# rgb_led_watch.net
KiCad netlist of a schematic drawn in EAGLE
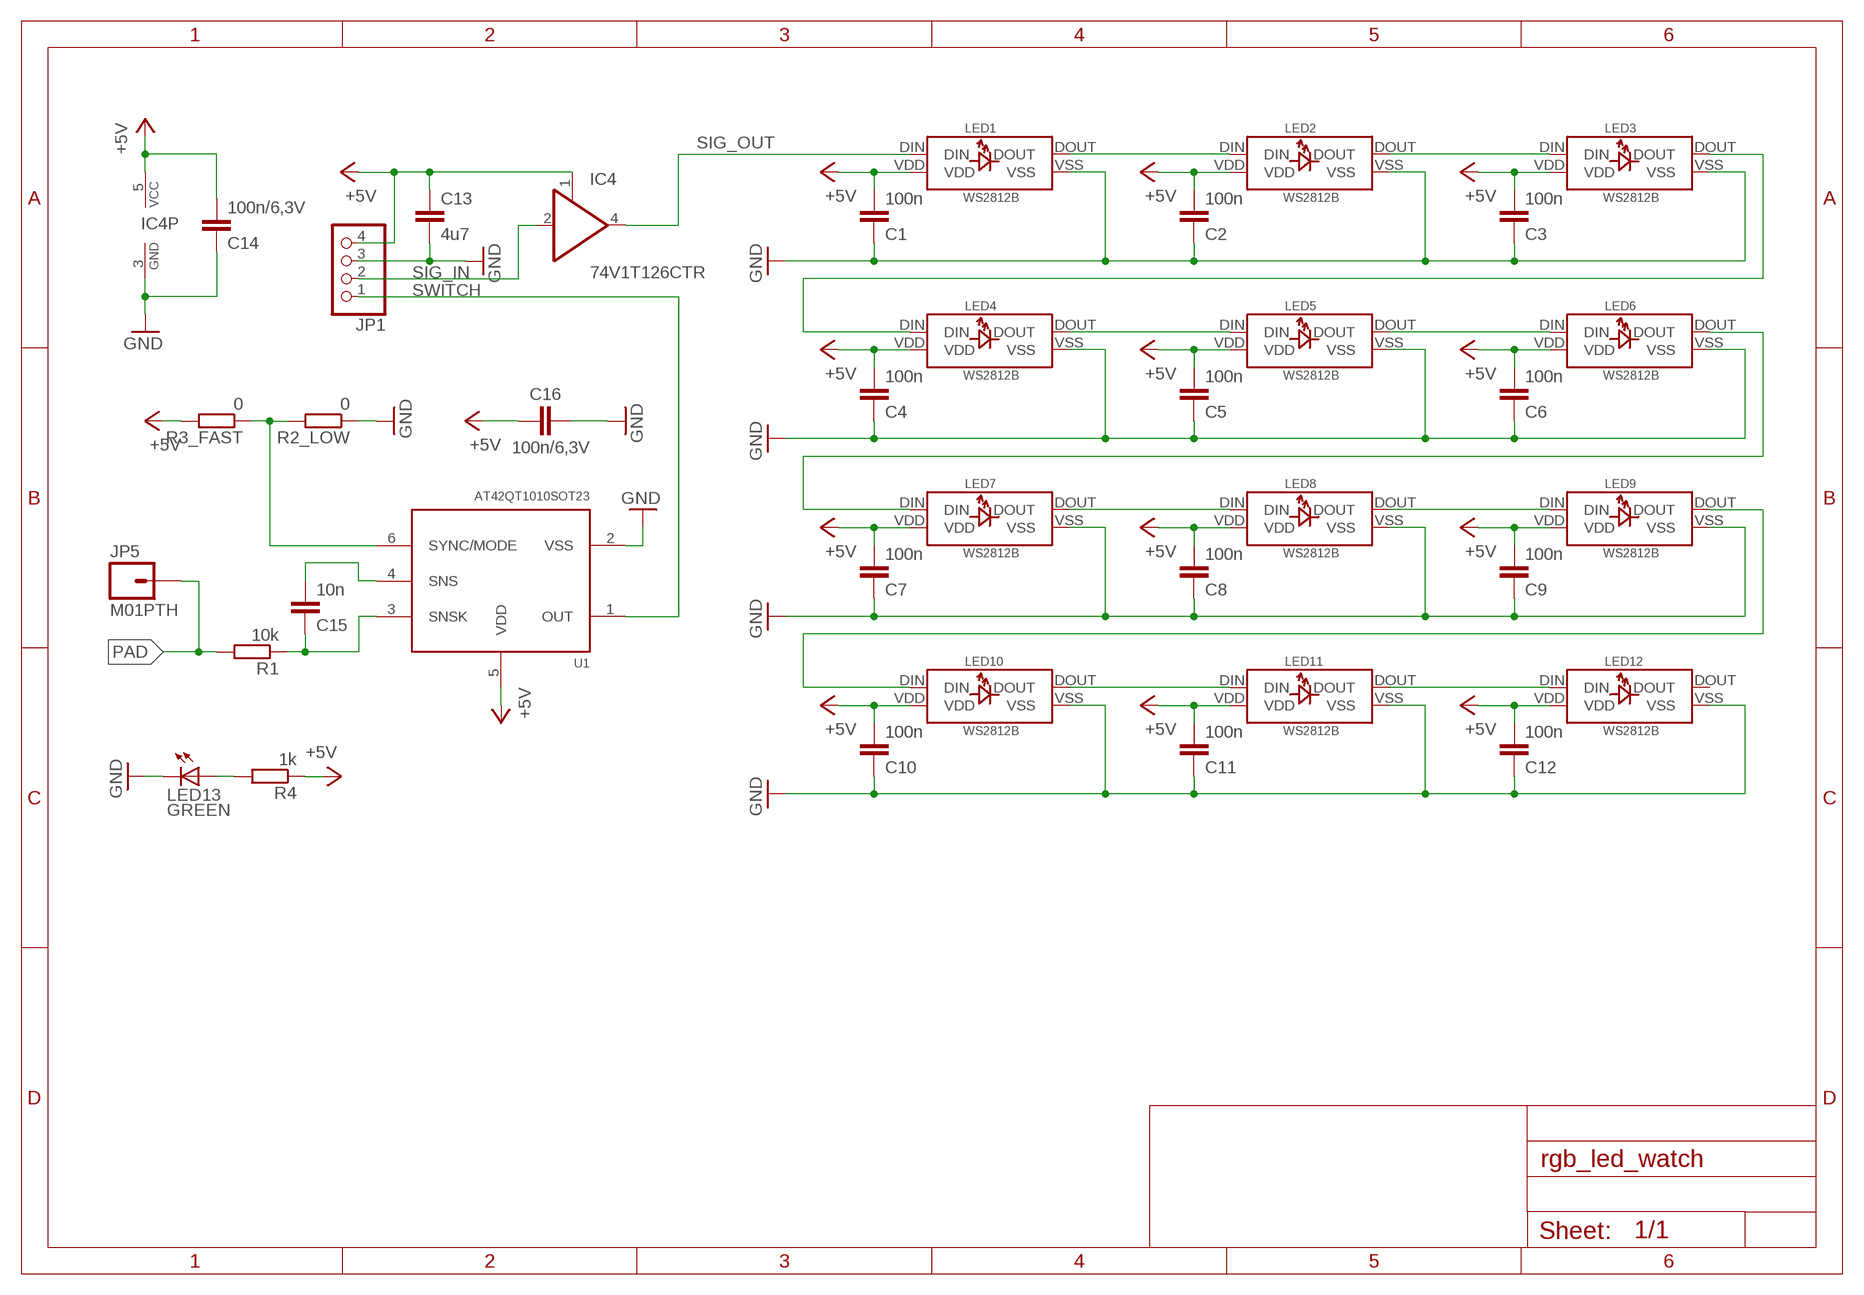
[diagram p0: schematic, sheet 1]

(export (version "E")
  (design (tool "Eeschema 10.0.6"))
  (components
    (comp (ref "C1")
      (value "100n")
      (footprint "eagle-import:C0603")
      (libsource (lib "eagle-import") (part "resistor_C-EUC0603"))
    )
    (comp (ref "C2")
      (value "100n")
      (footprint "eagle-import:C0603")
      (libsource (lib "eagle-import") (part "resistor_C-EUC0603"))
    )
    (comp (ref "C3")
      (value "100n")
      (footprint "eagle-import:C0603")
      (libsource (lib "eagle-import") (part "resistor_C-EUC0603"))
    )
    (comp (ref "C4")
      (value "100n")
      (footprint "eagle-import:C0603")
      (libsource (lib "eagle-import") (part "resistor_C-EUC0603"))
    )
    (comp (ref "C5")
      (value "100n")
      (footprint "eagle-import:C0603")
      (libsource (lib "eagle-import") (part "resistor_C-EUC0603"))
    )
    (comp (ref "C6")
      (value "100n")
      (footprint "eagle-import:C0603")
      (libsource (lib "eagle-import") (part "resistor_C-EUC0603"))
    )
    (comp (ref "C7")
      (value "100n")
      (footprint "eagle-import:C0603")
      (libsource (lib "eagle-import") (part "resistor_C-EUC0603"))
    )
    (comp (ref "C8")
      (value "100n")
      (footprint "eagle-import:C0603")
      (libsource (lib "eagle-import") (part "resistor_C-EUC0603"))
    )
    (comp (ref "C9")
      (value "100n")
      (footprint "eagle-import:C0603")
      (libsource (lib "eagle-import") (part "resistor_C-EUC0603"))
    )
    (comp (ref "C10")
      (value "100n")
      (footprint "eagle-import:C0603")
      (libsource (lib "eagle-import") (part "resistor_C-EUC0603"))
    )
    (comp (ref "C11")
      (value "100n")
      (footprint "eagle-import:C0603")
      (libsource (lib "eagle-import") (part "resistor_C-EUC0603"))
    )
    (comp (ref "C12")
      (value "100n")
      (footprint "eagle-import:C0603")
      (libsource (lib "eagle-import") (part "resistor_C-EUC0603"))
    )
    (comp (ref "C13")
      (value "4u7")
      (footprint "eagle-import:C0603")
      (libsource (lib "eagle-import") (part "C-EUC0603"))
    )
    (comp (ref "C14")
      (value "100n/6,3V")
      (footprint "eagle-import:C0603")
      (libsource (lib "eagle-import") (part "C-EUC0603"))
    )
    (comp (ref "C15")
      (value "10n")
      (footprint "eagle-import:C0603")
      (libsource (lib "eagle-import") (part "C-EUC0603"))
    )
    (comp (ref "C16")
      (value "100n/6,3V")
      (footprint "eagle-import:C0603")
      (libsource (lib "eagle-import") (part "C-EUC0603"))
    )
    (comp (ref "IC4")
      (value "74V1T126CTR")
      (footprint "eagle-import:SC70-5")
      (libsource (lib "eagle-import") (part "741G126DCKAHC"))
    )
    (comp (ref "JP1")
      (value "PINHD-1X4/90")
      (footprint "eagle-import:1X04_90")
      (libsource (lib "eagle-import") (part "PINHD-1X4/90"))
    )
    (comp (ref "JP5")
      (value "M01PTH")
      (footprint "eagle-import:1X01")
      (libsource (lib "eagle-import") (part "M01PTH"))
    )
    (comp (ref "LED1")
      (value "WS2812B")
      (footprint "eagle-import:WS2812B")
      (libsource (lib "eagle-import") (part "WS2812B"))
    )
    (comp (ref "LED2")
      (value "WS2812B")
      (footprint "eagle-import:WS2812B")
      (libsource (lib "eagle-import") (part "WS2812B"))
    )
    (comp (ref "LED3")
      (value "WS2812B")
      (footprint "eagle-import:WS2812B")
      (libsource (lib "eagle-import") (part "WS2812B"))
    )
    (comp (ref "LED4")
      (value "WS2812B")
      (footprint "eagle-import:WS2812B")
      (libsource (lib "eagle-import") (part "WS2812B"))
    )
    (comp (ref "LED5")
      (value "WS2812B")
      (footprint "eagle-import:WS2812B")
      (libsource (lib "eagle-import") (part "WS2812B"))
    )
    (comp (ref "LED6")
      (value "WS2812B")
      (footprint "eagle-import:WS2812B")
      (libsource (lib "eagle-import") (part "WS2812B"))
    )
    (comp (ref "LED7")
      (value "WS2812B")
      (footprint "eagle-import:WS2812B")
      (libsource (lib "eagle-import") (part "WS2812B"))
    )
    (comp (ref "LED8")
      (value "WS2812B")
      (footprint "eagle-import:WS2812B")
      (libsource (lib "eagle-import") (part "WS2812B"))
    )
    (comp (ref "LED9")
      (value "WS2812B")
      (footprint "eagle-import:WS2812B")
      (libsource (lib "eagle-import") (part "WS2812B"))
    )
    (comp (ref "LED10")
      (value "WS2812B")
      (footprint "eagle-import:WS2812B")
      (libsource (lib "eagle-import") (part "WS2812B"))
    )
    (comp (ref "LED11")
      (value "WS2812B")
      (footprint "eagle-import:WS2812B")
      (libsource (lib "eagle-import") (part "WS2812B"))
    )
    (comp (ref "LED12")
      (value "WS2812B")
      (footprint "eagle-import:WS2812B")
      (libsource (lib "eagle-import") (part "WS2812B"))
    )
    (comp (ref "LED13")
      (value "GREEN")
      (footprint "eagle-import:CHIPLED_0603")
      (libsource (lib "eagle-import") (part "LEDCHIPLED_0603"))
    )
    (comp (ref "R1")
      (value "10k")
      (footprint "eagle-import:R0603")
      (libsource (lib "eagle-import") (part "R-EU_R0603"))
    )
    (comp (ref "R2_LOW")
      (value "0")
      (footprint "eagle-import:R0603")
      (libsource (lib "eagle-import") (part "R-EU_R0603"))
    )
    (comp (ref "R3_FAST")
      (value "0")
      (footprint "eagle-import:R0603")
      (libsource (lib "eagle-import") (part "R-EU_R0603"))
    )
    (comp (ref "R4")
      (value "1k")
      (footprint "eagle-import:R0603")
      (libsource (lib "eagle-import") (part "rcl_upravena_R-EU_R0603"))
    )
    (comp (ref "U1")
      (value "AT42QT1010SOT23")
      (footprint "eagle-import:SOT23-6")
      (libsource (lib "eagle-import") (part "AT42QT1010SOT23"))
    )
  )
  (nets
    (net (code "1") (name "+5V") (class "Default")
      (node (ref "C1") (pin "2") (pinfunction "2_2") (pintype "passive"))
      (node (ref "C10") (pin "2") (pinfunction "2_2") (pintype "passive"))
      (node (ref "C11") (pin "2") (pinfunction "2_2") (pintype "passive"))
      (node (ref "C12") (pin "2") (pinfunction "2_2") (pintype "passive"))
      (node (ref "C13") (pin "1") (pinfunction "1_1") (pintype "passive"))
      (node (ref "C14") (pin "2") (pinfunction "2_2") (pintype "passive"))
      (node (ref "C16") (pin "1") (pinfunction "1_1") (pintype "passive"))
      (node (ref "C2") (pin "2") (pinfunction "2_2") (pintype "passive"))
      (node (ref "C3") (pin "2") (pinfunction "2_2") (pintype "passive"))
      (node (ref "C4") (pin "2") (pinfunction "2_2") (pintype "passive"))
      (node (ref "C5") (pin "2") (pinfunction "2_2") (pintype "passive"))
      (node (ref "C6") (pin "2") (pinfunction "2_2") (pintype "passive"))
      (node (ref "C7") (pin "2") (pinfunction "2_2") (pintype "passive"))
      (node (ref "C8") (pin "2") (pinfunction "2_2") (pintype "passive"))
      (node (ref "C9") (pin "2") (pinfunction "2_2") (pintype "passive"))
      (node (ref "IC4") (pin "1") (pinfunction "OE_1") (pintype "input"))
      (node (ref "IC4") (pin "5") (pinfunction "VCC_5") (pintype "power_in"))
      (node (ref "JP1") (pin "4") (pinfunction "4_4") (pintype "passive"))
      (node (ref "LED1") (pin "VDD") (pinfunction "VDD_VDD") (pintype "power_in"))
      (node (ref "LED10") (pin "VDD") (pinfunction "VDD_VDD") (pintype "power_in"))
      (node (ref "LED11") (pin "VDD") (pinfunction "VDD_VDD") (pintype "power_in"))
      (node (ref "LED12") (pin "VDD") (pinfunction "VDD_VDD") (pintype "power_in"))
      (node (ref "LED2") (pin "VDD") (pinfunction "VDD_VDD") (pintype "power_in"))
      (node (ref "LED3") (pin "VDD") (pinfunction "VDD_VDD") (pintype "power_in"))
      (node (ref "LED4") (pin "VDD") (pinfunction "VDD_VDD") (pintype "power_in"))
      (node (ref "LED5") (pin "VDD") (pinfunction "VDD_VDD") (pintype "power_in"))
      (node (ref "LED6") (pin "VDD") (pinfunction "VDD_VDD") (pintype "power_in"))
      (node (ref "LED7") (pin "VDD") (pinfunction "VDD_VDD") (pintype "power_in"))
      (node (ref "LED8") (pin "VDD") (pinfunction "VDD_VDD") (pintype "power_in"))
      (node (ref "LED9") (pin "VDD") (pinfunction "VDD_VDD") (pintype "power_in"))
      (node (ref "R3_FAST") (pin "2") (pinfunction "2_2") (pintype "passive"))
      (node (ref "R4") (pin "1") (pinfunction "1_1") (pintype "passive"))
      (node (ref "U1") (pin "5") (pinfunction "VDD_5") (pintype "bidirectional"))
    )
    (net (code "2") (name "/SIG_IN") (class "Default")
      (node (ref "IC4") (pin "2") (pinfunction "I_2") (pintype "input"))
      (node (ref "JP1") (pin "2") (pinfunction "2_2") (pintype "passive"))
    )
    (net (code "3") (name "/SIG_OUT") (class "Default")
      (node (ref "IC4") (pin "4") (pinfunction "O_4") (pintype "output"))
      (node (ref "LED1") (pin "DIN") (pinfunction "DIN_DIN") (pintype "input"))
    )
    (net (code "4") (name "/SWITCH") (class "Default")
      (node (ref "JP1") (pin "1") (pinfunction "1_1") (pintype "passive"))
      (node (ref "U1") (pin "1") (pinfunction "OUT_1") (pintype "bidirectional"))
    )
    (net (code "5") (name "GND") (class "Default")
      (node (ref "C1") (pin "1") (pinfunction "1_1") (pintype "passive"))
      (node (ref "C10") (pin "1") (pinfunction "1_1") (pintype "passive"))
      (node (ref "C11") (pin "1") (pinfunction "1_1") (pintype "passive"))
      (node (ref "C12") (pin "1") (pinfunction "1_1") (pintype "passive"))
      (node (ref "C13") (pin "2") (pinfunction "2_2") (pintype "passive"))
      (node (ref "C14") (pin "1") (pinfunction "1_1") (pintype "passive"))
      (node (ref "C16") (pin "2") (pinfunction "2_2") (pintype "passive"))
      (node (ref "C2") (pin "1") (pinfunction "1_1") (pintype "passive"))
      (node (ref "C3") (pin "1") (pinfunction "1_1") (pintype "passive"))
      (node (ref "C4") (pin "1") (pinfunction "1_1") (pintype "passive"))
      (node (ref "C5") (pin "1") (pinfunction "1_1") (pintype "passive"))
      (node (ref "C6") (pin "1") (pinfunction "1_1") (pintype "passive"))
      (node (ref "C7") (pin "1") (pinfunction "1_1") (pintype "passive"))
      (node (ref "C8") (pin "1") (pinfunction "1_1") (pintype "passive"))
      (node (ref "C9") (pin "1") (pinfunction "1_1") (pintype "passive"))
      (node (ref "IC4") (pin "3") (pinfunction "GND_3") (pintype "power_in"))
      (node (ref "JP1") (pin "3") (pinfunction "3_3") (pintype "passive"))
      (node (ref "LED1") (pin "VSS") (pinfunction "VSS_VSS") (pintype "power_in"))
      (node (ref "LED10") (pin "VSS") (pinfunction "VSS_VSS") (pintype "power_in"))
      (node (ref "LED11") (pin "VSS") (pinfunction "VSS_VSS") (pintype "power_in"))
      (node (ref "LED12") (pin "VSS") (pinfunction "VSS_VSS") (pintype "power_in"))
      (node (ref "LED13") (pin "C") (pinfunction "C_C") (pintype "passive"))
      (node (ref "LED2") (pin "VSS") (pinfunction "VSS_VSS") (pintype "power_in"))
      (node (ref "LED3") (pin "VSS") (pinfunction "VSS_VSS") (pintype "power_in"))
      (node (ref "LED4") (pin "VSS") (pinfunction "VSS_VSS") (pintype "power_in"))
      (node (ref "LED5") (pin "VSS") (pinfunction "VSS_VSS") (pintype "power_in"))
      (node (ref "LED6") (pin "VSS") (pinfunction "VSS_VSS") (pintype "power_in"))
      (node (ref "LED7") (pin "VSS") (pinfunction "VSS_VSS") (pintype "power_in"))
      (node (ref "LED8") (pin "VSS") (pinfunction "VSS_VSS") (pintype "power_in"))
      (node (ref "LED9") (pin "VSS") (pinfunction "VSS_VSS") (pintype "power_in"))
      (node (ref "R2_LOW") (pin "1") (pinfunction "1_1") (pintype "passive"))
      (node (ref "U1") (pin "2") (pinfunction "VSS_2") (pintype "bidirectional"))
    )
    (net (code "6") (name "Net-(LED1-PadDOUT)") (class "Default")
      (node (ref "LED1") (pin "DOUT") (pinfunction "DOUT_DOUT") (pintype "output"))
      (node (ref "LED2") (pin "DIN") (pinfunction "DIN_DIN") (pintype "input"))
    )
    (net (code "7") (name "Net-(LED2-PadDOUT)") (class "Default")
      (node (ref "LED2") (pin "DOUT") (pinfunction "DOUT_DOUT") (pintype "output"))
      (node (ref "LED3") (pin "DIN") (pinfunction "DIN_DIN") (pintype "input"))
    )
    (net (code "8") (name "Net-(LED3-PadDOUT)") (class "Default")
      (node (ref "LED3") (pin "DOUT") (pinfunction "DOUT_DOUT") (pintype "output"))
      (node (ref "LED4") (pin "DIN") (pinfunction "DIN_DIN") (pintype "input"))
    )
    (net (code "9") (name "Net-(LED4-PadDOUT)") (class "Default")
      (node (ref "LED4") (pin "DOUT") (pinfunction "DOUT_DOUT") (pintype "output"))
      (node (ref "LED5") (pin "DIN") (pinfunction "DIN_DIN") (pintype "input"))
    )
    (net (code "10") (name "Net-(LED5-PadDOUT)") (class "Default")
      (node (ref "LED5") (pin "DOUT") (pinfunction "DOUT_DOUT") (pintype "output"))
      (node (ref "LED6") (pin "DIN") (pinfunction "DIN_DIN") (pintype "input"))
    )
    (net (code "11") (name "Net-(LED6-PadDOUT)") (class "Default")
      (node (ref "LED6") (pin "DOUT") (pinfunction "DOUT_DOUT") (pintype "output"))
      (node (ref "LED7") (pin "DIN") (pinfunction "DIN_DIN") (pintype "input"))
    )
    (net (code "12") (name "Net-(LED7-PadDOUT)") (class "Default")
      (node (ref "LED7") (pin "DOUT") (pinfunction "DOUT_DOUT") (pintype "output"))
      (node (ref "LED8") (pin "DIN") (pinfunction "DIN_DIN") (pintype "input"))
    )
    (net (code "13") (name "Net-(LED8-PadDOUT)") (class "Default")
      (node (ref "LED8") (pin "DOUT") (pinfunction "DOUT_DOUT") (pintype "output"))
      (node (ref "LED9") (pin "DIN") (pinfunction "DIN_DIN") (pintype "input"))
    )
    (net (code "14") (name "Net-(LED10-PadDIN)") (class "Default")
      (node (ref "LED10") (pin "DIN") (pinfunction "DIN_DIN") (pintype "input"))
      (node (ref "LED9") (pin "DOUT") (pinfunction "DOUT_DOUT") (pintype "output"))
    )
    (net (code "15") (name "Net-(LED10-PadDOUT)") (class "Default")
      (node (ref "LED10") (pin "DOUT") (pinfunction "DOUT_DOUT") (pintype "output"))
      (node (ref "LED11") (pin "DIN") (pinfunction "DIN_DIN") (pintype "input"))
    )
    (net (code "16") (name "Net-(LED11-PadDOUT)") (class "Default")
      (node (ref "LED11") (pin "DOUT") (pinfunction "DOUT_DOUT") (pintype "output"))
      (node (ref "LED12") (pin "DIN") (pinfunction "DIN_DIN") (pintype "input"))
    )
    (net (code "17") (name "Net-(LED13-PadA)") (class "Default")
      (node (ref "LED13") (pin "A") (pinfunction "A_A") (pintype "passive"))
      (node (ref "R4") (pin "2") (pinfunction "2_2") (pintype "passive"))
    )
    (net (code "18") (name "Net-(U1-SNS)") (class "Default")
      (node (ref "C15") (pin "2") (pinfunction "2_2") (pintype "passive"))
      (node (ref "U1") (pin "4") (pinfunction "SNS_4") (pintype "bidirectional"))
    )
    (net (code "19") (name "Net-(U1-SNSK)") (class "Default")
      (node (ref "C15") (pin "1") (pinfunction "1_1") (pintype "passive"))
      (node (ref "R1") (pin "1") (pinfunction "1_1") (pintype "passive"))
      (node (ref "U1") (pin "3") (pinfunction "SNSK_3") (pintype "bidirectional"))
    )
    (net (code "20") (name "Net-(U1-SYNC{slash}MODE)") (class "Default")
      (node (ref "R2_LOW") (pin "2") (pinfunction "2_2") (pintype "passive"))
      (node (ref "R3_FAST") (pin "1") (pinfunction "1_1") (pintype "passive"))
      (node (ref "U1") (pin "6") (pinfunction "SYNC/MODE_6") (pintype "bidirectional"))
    )
    (net (code "21") (name "PAD") (class "Default")
      (node (ref "JP5") (pin "1") (pinfunction "1_1") (pintype "passive"))
      (node (ref "R1") (pin "2") (pinfunction "2_2") (pintype "passive"))
    )
    (net (code "22") (name "unconnected-(LED12-PadDOUT)") (class "Default")
      (node (ref "LED12") (pin "DOUT") (pinfunction "DOUT_DOUT") (pintype "output"))
    )
  )
)
